# untitled.net
KiCad netlist of a schematic drawn in EAGLE
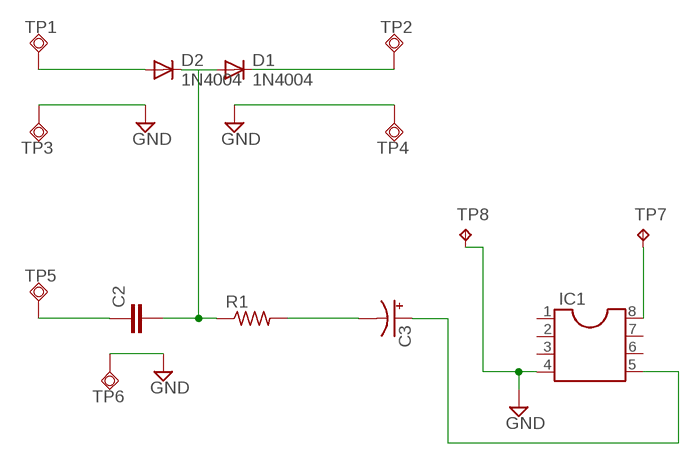
[diagram p0: schematic, sheet 1]

(export (version "E")
  (design (tool "Eeschema 10.0.6"))
  (components
    (comp (ref "C2")
      (value "C5/3")
      (footprint "eagle-import:C5B3")
      (libsource (lib "eagle-import") (part "C5/3"))
    )
    (comp (ref "C3")
      (value "CPOL-USE5-6")
      (footprint "eagle-import:E5-6")
      (libsource (lib "eagle-import") (part "CPOL-USE5-6"))
    )
    (comp (ref "D1")
      (value "1N4004")
      (footprint "eagle-import:DO41-10")
      (libsource (lib "eagle-import") (part "diode_1N4004"))
    )
    (comp (ref "D2")
      (value "1N4004")
      (footprint "eagle-import:DO41-10")
      (libsource (lib "eagle-import") (part "1N4004"))
    )
    (comp (ref "IC1")
      (value "DIL8S")
      (footprint "eagle-import:SOCKET-08")
      (libsource (lib "eagle-import") (part "DIL8S"))
    )
    (comp (ref "R1")
      (value "R-US_0204/7")
      (footprint "eagle-import:0204_7")
      (libsource (lib "eagle-import") (part "R-US_0204/7"))
    )
    (comp (ref "TP1")
      (value "TPSQPAD1-20Y")
      (footprint "eagle-import:P1-20Y")
      (libsource (lib "eagle-import") (part "TPSQPAD1-20Y"))
    )
    (comp (ref "TP2")
      (value "TPSQPAD1-20Y")
      (footprint "eagle-import:P1-20Y")
      (libsource (lib "eagle-import") (part "TPSQPAD1-20Y"))
    )
    (comp (ref "TP3")
      (value "TPSQPAD1-20Y")
      (footprint "eagle-import:P1-20Y")
      (libsource (lib "eagle-import") (part "TPSQPAD1-20Y"))
    )
    (comp (ref "TP4")
      (value "TPSQPAD1-20Y")
      (footprint "eagle-import:P1-20Y")
      (libsource (lib "eagle-import") (part "TPSQPAD1-20Y"))
    )
    (comp (ref "TP5")
      (value "TPSQPAD1-20Y")
      (footprint "eagle-import:P1-20Y")
      (libsource (lib "eagle-import") (part "TPSQPAD1-20Y"))
    )
    (comp (ref "TP6")
      (value "TPSQPAD1-20Y")
      (footprint "eagle-import:P1-20Y")
      (libsource (lib "eagle-import") (part "TPSQPAD1-20Y"))
    )
    (comp (ref "TP7")
      (value "TPPAD1-20")
      (footprint "eagle-import:P1-20")
      (libsource (lib "eagle-import") (part "TPPAD1-20"))
    )
    (comp (ref "TP8")
      (value "TPPAD1-20Y")
      (footprint "eagle-import:P1-20Y")
      (libsource (lib "eagle-import") (part "TPPAD1-20Y"))
    )
  )
  (nets
    (net (code "1") (name "GND") (class "Default")
      (node (ref "IC1") (pin "4") (pinfunction "4_4") (pintype "passive"))
      (node (ref "TP3") (pin "TP") (pinfunction "TP_TP") (pintype "input"))
      (node (ref "TP4") (pin "TP") (pinfunction "TP_TP") (pintype "input"))
      (node (ref "TP6") (pin "TP") (pinfunction "TP_TP") (pintype "input"))
      (node (ref "TP8") (pin "TP") (pinfunction "TP_TP") (pintype "input"))
    )
    (net (code "2") (name "Net-(C2-Pad1)") (class "Default")
      (node (ref "C2") (pin "1") (pinfunction "1_1") (pintype "passive"))
      (node (ref "TP5") (pin "TP") (pinfunction "TP_TP") (pintype "input"))
    )
    (net (code "3") (name "Net-(C2-Pad2)") (class "Default")
      (node (ref "C2") (pin "2") (pinfunction "2_2") (pintype "passive"))
      (node (ref "D1") (pin "A") (pinfunction "A_A") (pintype "passive"))
      (node (ref "D2") (pin "C") (pinfunction "C_C") (pintype "passive"))
      (node (ref "R1") (pin "1") (pinfunction "1_1") (pintype "passive"))
    )
    (net (code "4") (name "Net-(C3-Pad+)") (class "Default")
      (node (ref "C3") (pin "+") (pinfunction "+_+") (pintype "passive"))
      (node (ref "IC1") (pin "5") (pinfunction "5_5") (pintype "passive"))
    )
    (net (code "5") (name "Net-(C3-Pad-)") (class "Default")
      (node (ref "C3") (pin "-") (pinfunction "-_-") (pintype "passive"))
      (node (ref "R1") (pin "2") (pinfunction "2_2") (pintype "passive"))
    )
    (net (code "6") (name "Net-(D1-PadC)") (class "Default")
      (node (ref "D1") (pin "C") (pinfunction "C_C") (pintype "passive"))
      (node (ref "TP2") (pin "TP") (pinfunction "TP_TP") (pintype "input"))
    )
    (net (code "7") (name "Net-(D2-PadA)") (class "Default")
      (node (ref "D2") (pin "A") (pinfunction "A_A") (pintype "passive"))
      (node (ref "TP1") (pin "TP") (pinfunction "TP_TP") (pintype "input"))
    )
    (net (code "8") (name "Net-(IC1-Pad8)") (class "Default")
      (node (ref "IC1") (pin "8") (pinfunction "8_8") (pintype "passive"))
      (node (ref "TP7") (pin "TP") (pinfunction "TP_TP") (pintype "input"))
    )
    (net (code "9") (name "unconnected-(IC1-Pad1)") (class "Default")
      (node (ref "IC1") (pin "1") (pinfunction "1_1") (pintype "passive"))
    )
    (net (code "10") (name "unconnected-(IC1-Pad2)") (class "Default")
      (node (ref "IC1") (pin "2") (pinfunction "2_2") (pintype "passive"))
    )
    (net (code "11") (name "unconnected-(IC1-Pad3)") (class "Default")
      (node (ref "IC1") (pin "3") (pinfunction "3_3") (pintype "passive"))
    )
    (net (code "12") (name "unconnected-(IC1-Pad6)") (class "Default")
      (node (ref "IC1") (pin "6") (pinfunction "6_6") (pintype "passive"))
    )
    (net (code "13") (name "unconnected-(IC1-Pad7)") (class "Default")
      (node (ref "IC1") (pin "7") (pinfunction "7_7") (pintype "passive"))
    )
  )
)
